# Street_Fighter_v1_1.net
KiCad netlist of a schematic drawn in EAGLE
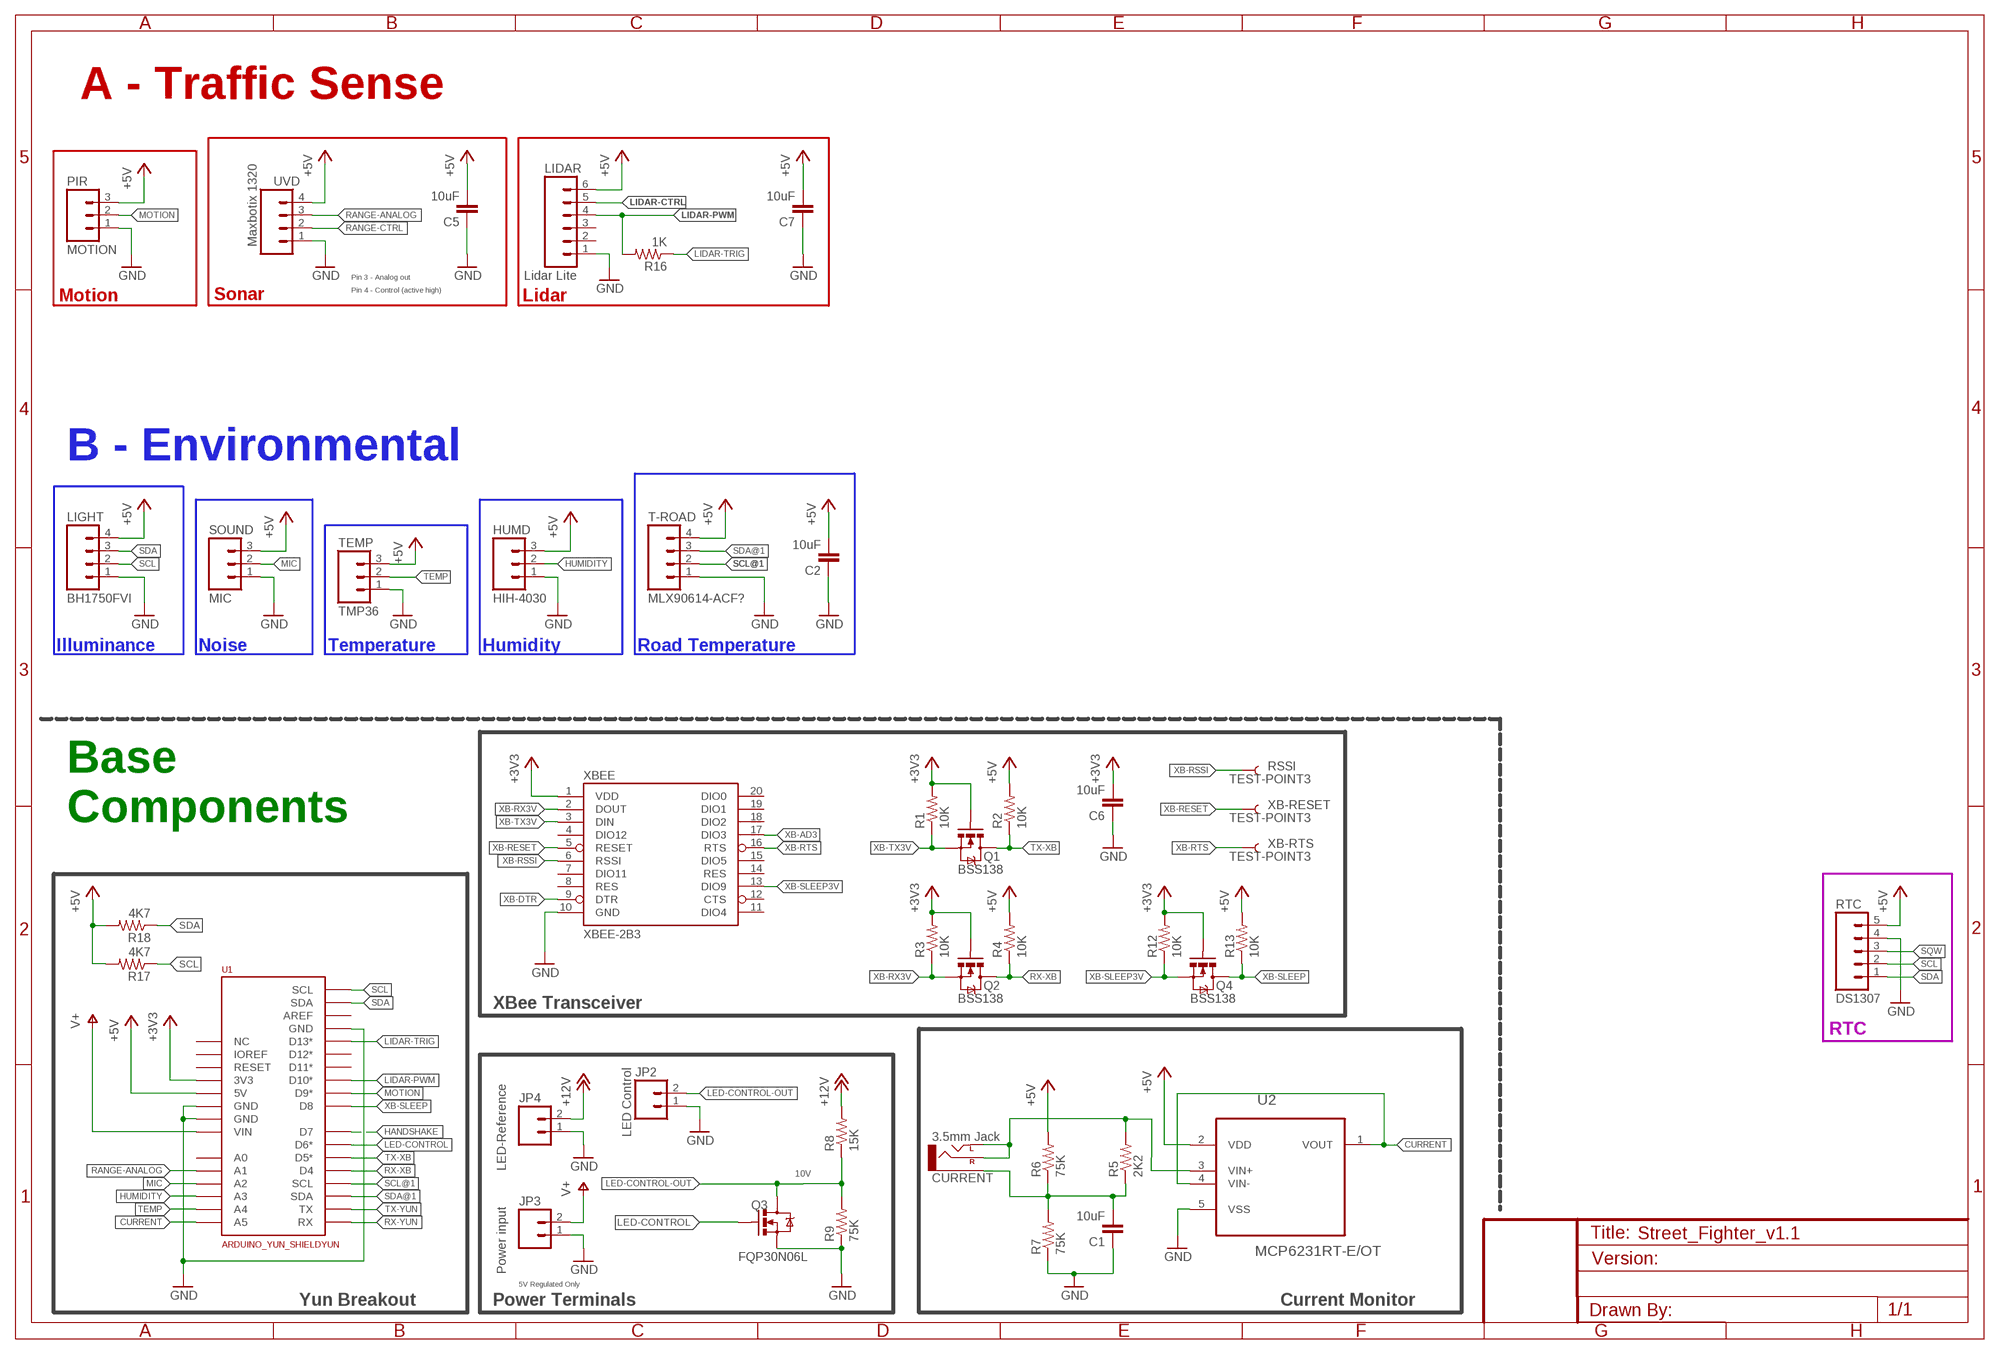
[diagram p0: schematic, sheet 1]

(export (version "E")
  (design (tool "Eeschema 10.0.6"))
  (components
    (comp (ref "C1")
      (value "10uF")
      (footprint "eagle-import:1206")
      (libsource (lib "eagle-import") (part "10UF-6.3V-20%(1206)"))
    )
    (comp (ref "C2")
      (value "10uF")
      (footprint "eagle-import:1206")
      (libsource (lib "eagle-import") (part "10UF-6.3V-20%(1206)"))
    )
    (comp (ref "C5")
      (value "10uF")
      (footprint "eagle-import:1206")
      (libsource (lib "eagle-import") (part "10UF-6.3V-20%(1206)"))
    )
    (comp (ref "C6")
      (value "10uF")
      (footprint "eagle-import:1206")
      (libsource (lib "eagle-import") (part "10UF-6.3V-20%(1206)"))
    )
    (comp (ref "C7")
      (value "10uF")
      (footprint "eagle-import:1206")
      (libsource (lib "eagle-import") (part "10UF-6.3V-20%(1206)"))
    )
    (comp (ref "CURRENT")
      (value "3.5mm Jack")
      (footprint "eagle-import:AUDIO-JACK")
      (libsource (lib "eagle-import") (part "AUDIO-JACKPTH"))
    )
    (comp (ref "HUMD")
      (value "HIH-4030")
      (footprint "eagle-import:1X03")
      (libsource (lib "eagle-import") (part "M03PTH"))
    )
    (comp (ref "JP2")
      (value "LED Control")
      (footprint "eagle-import:1X02_LONGPADS")
      (libsource (lib "eagle-import") (part "M02PTH3"))
    )
    (comp (ref "JP3")
      (value "Power input")
      (footprint "eagle-import:1X02_LONGPADS")
      (libsource (lib "eagle-import") (part "M02PTH3"))
    )
    (comp (ref "JP4")
      (value "LED-Reference")
      (footprint "eagle-import:1X02_LONGPADS")
      (libsource (lib "eagle-import") (part "M02PTH3"))
    )
    (comp (ref "LIDAR")
      (value "Lidar Lite")
      (footprint "eagle-import:1X06")
      (libsource (lib "eagle-import") (part "M06SIP"))
    )
    (comp (ref "LIGHT")
      (value "BH1750FVI")
      (footprint "eagle-import:1X04")
      (libsource (lib "eagle-import") (part "M04PTH"))
    )
    (comp (ref "PIR")
      (value "MOTION")
      (footprint "eagle-import:1X03")
      (libsource (lib "eagle-import") (part "M03PTH"))
    )
    (comp (ref "Q1")
      (value "BSS138")
      (footprint "eagle-import:SOT23")
      (libsource (lib "eagle-import") (part "MOSFET-NCHANNELBSS123LT1G"))
    )
    (comp (ref "Q2")
      (value "BSS138")
      (footprint "eagle-import:SOT23")
      (libsource (lib "eagle-import") (part "MOSFET-NCHANNELBSS123LT1G"))
    )
    (comp (ref "Q3")
      (value "FQP30N06L")
      (footprint "eagle-import:TO220V")
      (libsource (lib "eagle-import") (part "MOSFET-NCHANNELFQP30N06L"))
    )
    (comp (ref "Q4")
      (value "BSS138")
      (footprint "eagle-import:SOT23")
      (libsource (lib "eagle-import") (part "MOSFET-NCHANNELBSS123LT1G"))
    )
    (comp (ref "R1")
      (value "10K")
      (footprint "eagle-import:1206")
      (libsource (lib "eagle-import") (part "RESISTOR1206"))
    )
    (comp (ref "R2")
      (value "10K")
      (footprint "eagle-import:1206")
      (libsource (lib "eagle-import") (part "RESISTOR1206"))
    )
    (comp (ref "R3")
      (value "10K")
      (footprint "eagle-import:1206")
      (libsource (lib "eagle-import") (part "RESISTOR1206"))
    )
    (comp (ref "R4")
      (value "10K")
      (footprint "eagle-import:1206")
      (libsource (lib "eagle-import") (part "RESISTOR1206"))
    )
    (comp (ref "R5")
      (value "2K2")
      (footprint "eagle-import:1206")
      (libsource (lib "eagle-import") (part "RESISTOR1206"))
    )
    (comp (ref "R6")
      (value "75K")
      (footprint "eagle-import:1206")
      (libsource (lib "eagle-import") (part "RESISTOR1206"))
    )
    (comp (ref "R7")
      (value "75K")
      (footprint "eagle-import:1206")
      (libsource (lib "eagle-import") (part "RESISTOR1206"))
    )
    (comp (ref "R8")
      (value "15K")
      (footprint "eagle-import:1206")
      (libsource (lib "eagle-import") (part "RESISTOR1206"))
    )
    (comp (ref "R9")
      (value "75K")
      (footprint "eagle-import:1206")
      (libsource (lib "eagle-import") (part "RESISTOR1206"))
    )
    (comp (ref "R12")
      (value "10K")
      (footprint "eagle-import:1206")
      (libsource (lib "eagle-import") (part "RESISTOR1206"))
    )
    (comp (ref "R13")
      (value "10K")
      (footprint "eagle-import:1206")
      (libsource (lib "eagle-import") (part "RESISTOR1206"))
    )
    (comp (ref "R16")
      (value "1K")
      (footprint "eagle-import:1206")
      (libsource (lib "eagle-import") (part "RESISTOR1206"))
    )
    (comp (ref "R17")
      (value "4K7")
      (footprint "eagle-import:1206")
      (libsource (lib "eagle-import") (part "RESISTOR1206"))
    )
    (comp (ref "R18")
      (value "4K7")
      (footprint "eagle-import:1206")
      (libsource (lib "eagle-import") (part "RESISTOR1206"))
    )
    (comp (ref "RSSI")
      (value "TEST-POINT3")
      (footprint "eagle-import:PAD.03X.03")
      (libsource (lib "eagle-import") (part "TEST-POINT3"))
    )
    (comp (ref "RTC")
      (value "DS1307")
      (footprint "eagle-import:1X05")
      (libsource (lib "eagle-import") (part "M05PTH"))
    )
    (comp (ref "SOUND")
      (value "MIC")
      (footprint "eagle-import:1X03")
      (libsource (lib "eagle-import") (part "M03PTH"))
    )
    (comp (ref "T-ROAD")
      (value "MLX90614-ACF?")
      (footprint "eagle-import:1X04")
      (libsource (lib "eagle-import") (part "M04PTH"))
    )
    (comp (ref "TEMP")
      (value "TMP36")
      (footprint "eagle-import:1X03")
      (libsource (lib "eagle-import") (part "M03PTH"))
    )
    (comp (ref "U1")
      (value "ARDUINO_YUN_SHIELDYUN")
      (footprint "eagle-import:DUEMILANOVE_VIAS")
      (libsource (lib "eagle-import") (part "ARDUINO_YUN_SHIELDYUN"))
    )
    (comp (ref "U2")
      (value "MCP6231RT-E/OT")
      (footprint "eagle-import:SOT95P270X145-5N")
      (libsource (lib "eagle-import") (part "MCP6231RT-E/OT"))
    )
    (comp (ref "UVD")
      (value "Maxbotix 1320")
      (footprint "eagle-import:1X04")
      (libsource (lib "eagle-import") (part "M04PTH"))
    )
    (comp (ref "XB-RESET")
      (value "TEST-POINT3")
      (footprint "eagle-import:PAD.03X.03")
      (libsource (lib "eagle-import") (part "TEST-POINT3"))
    )
    (comp (ref "XB-RTS")
      (value "TEST-POINT3")
      (footprint "eagle-import:PAD.03X.03")
      (libsource (lib "eagle-import") (part "TEST-POINT3"))
    )
    (comp (ref "XBEE")
      (value "XBEE-2B3")
      (footprint "eagle-import:XBEE-SMD")
      (libsource (lib "eagle-import") (part "XBEE-2B3"))
    )
  )
  (nets
    (net (code "1") (name "+3V3") (class "Default")
      (node (ref "C6") (pin "2") (pinfunction "2_2") (pintype "passive"))
      (node (ref "Q1") (pin "1") (pinfunction "G_1") (pintype "passive"))
      (node (ref "Q2") (pin "1") (pinfunction "G_1") (pintype "passive"))
      (node (ref "Q4") (pin "1") (pinfunction "G_1") (pintype "passive"))
      (node (ref "R1") (pin "2") (pinfunction "2_2") (pintype "passive"))
      (node (ref "R12") (pin "2") (pinfunction "2_2") (pintype "passive"))
      (node (ref "R3") (pin "2") (pinfunction "2_2") (pintype "passive"))
      (node (ref "U1") (pin "3V3") (pinfunction "3V3_3V3") (pintype "power_in"))
      (node (ref "XBEE") (pin "1") (pinfunction "VDD_1") (pintype "power_in"))
    )
    (net (code "2") (name "+5V") (class "Default")
      (node (ref "C2") (pin "2") (pinfunction "2_2") (pintype "passive"))
      (node (ref "C5") (pin "2") (pinfunction "2_2") (pintype "passive"))
      (node (ref "C7") (pin "2") (pinfunction "2_2") (pintype "passive"))
      (node (ref "HUMD") (pin "3") (pinfunction "3_3") (pintype "passive"))
      (node (ref "LIDAR") (pin "6") (pinfunction "6_6") (pintype "passive"))
      (node (ref "LIGHT") (pin "4") (pinfunction "4_4") (pintype "passive"))
      (node (ref "PIR") (pin "3") (pinfunction "3_3") (pintype "passive"))
      (node (ref "R13") (pin "2") (pinfunction "2_2") (pintype "passive"))
      (node (ref "R17") (pin "2") (pinfunction "2_2") (pintype "passive"))
      (node (ref "R18") (pin "2") (pinfunction "2_2") (pintype "passive"))
      (node (ref "R2") (pin "2") (pinfunction "2_2") (pintype "passive"))
      (node (ref "R4") (pin "2") (pinfunction "2_2") (pintype "passive"))
      (node (ref "R6") (pin "2") (pinfunction "2_2") (pintype "passive"))
      (node (ref "RTC") (pin "5") (pinfunction "5_5") (pintype "passive"))
      (node (ref "SOUND") (pin "3") (pinfunction "3_3") (pintype "passive"))
      (node (ref "T-ROAD") (pin "4") (pinfunction "4_4") (pintype "passive"))
      (node (ref "TEMP") (pin "3") (pinfunction "3_3") (pintype "passive"))
      (node (ref "U1") (pin "5V") (pinfunction "5V_5V") (pintype "power_in"))
      (node (ref "U2") (pin "2") (pinfunction "VDD_2") (pintype "power_in"))
      (node (ref "UVD") (pin "4") (pinfunction "4_4") (pintype "passive"))
    )
    (net (code "3") (name "+12V") (class "Default")
      (node (ref "JP4") (pin "2") (pinfunction "2_2") (pintype "passive"))
      (node (ref "R8") (pin "2") (pinfunction "2_2") (pintype "passive"))
    )
    (net (code "4") (name "CURRENT") (class "Default")
      (node (ref "U1") (pin "A5") (pinfunction "A5_A5") (pintype "bidirectional"))
      (node (ref "U2") (pin "1") (pinfunction "VOUT_1") (pintype "output"))
      (node (ref "U2") (pin "4") (pinfunction "VIN-_4") (pintype "input"))
    )
    (net (code "5") (name "GND") (class "Default")
      (node (ref "C1") (pin "1") (pinfunction "1_1") (pintype "passive"))
      (node (ref "C2") (pin "1") (pinfunction "1_1") (pintype "passive"))
      (node (ref "C5") (pin "1") (pinfunction "1_1") (pintype "passive"))
      (node (ref "C6") (pin "1") (pinfunction "1_1") (pintype "passive"))
      (node (ref "C7") (pin "1") (pinfunction "1_1") (pintype "passive"))
      (node (ref "HUMD") (pin "1") (pinfunction "1_1") (pintype "passive"))
      (node (ref "JP2") (pin "1") (pinfunction "1_1") (pintype "passive"))
      (node (ref "JP3") (pin "1") (pinfunction "1_1") (pintype "passive"))
      (node (ref "JP4") (pin "1") (pinfunction "1_1") (pintype "passive"))
      (node (ref "LIDAR") (pin "1") (pinfunction "1_1") (pintype "passive"))
      (node (ref "LIGHT") (pin "1") (pinfunction "1_1") (pintype "passive"))
      (node (ref "PIR") (pin "1") (pinfunction "1_1") (pintype "passive"))
      (node (ref "Q3") (pin "3") (pinfunction "S_3") (pintype "passive"))
      (node (ref "R7") (pin "1") (pinfunction "1_1") (pintype "passive"))
      (node (ref "R9") (pin "1") (pinfunction "1_1") (pintype "passive"))
      (node (ref "RTC") (pin "4") (pinfunction "4_4") (pintype "passive"))
      (node (ref "SOUND") (pin "1") (pinfunction "1_1") (pintype "passive"))
      (node (ref "T-ROAD") (pin "1") (pinfunction "1_1") (pintype "passive"))
      (node (ref "TEMP") (pin "1") (pinfunction "1_1") (pintype "passive"))
      (node (ref "U1") (pin "GND") (pinfunction "GND_GND") (pintype "power_in"))
      (node (ref "U1") (pin "GND@0") (pinfunction "GND_GND@0") (pintype "power_in"))
      (node (ref "U1") (pin "GND@1") (pinfunction "GND_GND@1") (pintype "power_in"))
      (node (ref "U2") (pin "5") (pinfunction "VSS_5") (pintype "passive"))
      (node (ref "UVD") (pin "1") (pinfunction "1_1") (pintype "passive"))
      (node (ref "XBEE") (pin "10") (pinfunction "GND_10") (pintype "power_in"))
    )
    (net (code "6") (name "HANDSHAKE") (class "Default")
      (node (ref "U1") (pin "7") (pinfunction "D7_7") (pintype "bidirectional"))
    )
    (net (code "7") (name "HUMIDITY") (class "Default")
      (node (ref "HUMD") (pin "2") (pinfunction "2_2") (pintype "passive"))
      (node (ref "U1") (pin "A3") (pinfunction "A3_A3") (pintype "bidirectional"))
    )
    (net (code "8") (name "LED-CONTROL") (class "Default")
      (node (ref "Q3") (pin "1") (pinfunction "G_1") (pintype "passive"))
      (node (ref "U1") (pin "6") (pinfunction "D6*_6") (pintype "bidirectional"))
    )
    (net (code "9") (name "LED-CONTROL-OUT") (class "Default")
      (node (ref "JP2") (pin "2") (pinfunction "2_2") (pintype "passive"))
      (node (ref "Q3") (pin "2") (pinfunction "D_2") (pintype "passive"))
      (node (ref "R8") (pin "1") (pinfunction "1_1") (pintype "passive"))
      (node (ref "R9") (pin "2") (pinfunction "2_2") (pintype "passive"))
    )
    (net (code "10") (name "LIDAR-CTRL") (class "Default")
      (node (ref "LIDAR") (pin "5") (pinfunction "5_5") (pintype "passive"))
    )
    (net (code "11") (name "LIDAR-PWM") (class "Default")
      (node (ref "LIDAR") (pin "4") (pinfunction "4_4") (pintype "passive"))
      (node (ref "R16") (pin "2") (pinfunction "2_2") (pintype "passive"))
      (node (ref "U1") (pin "10") (pinfunction "D10*_10") (pintype "bidirectional"))
    )
    (net (code "12") (name "LIDAR-TRIG") (class "Default")
      (node (ref "R16") (pin "1") (pinfunction "1_1") (pintype "passive"))
      (node (ref "U1") (pin "13") (pinfunction "D13*_13") (pintype "bidirectional"))
    )
    (net (code "13") (name "MIC") (class "Default")
      (node (ref "SOUND") (pin "2") (pinfunction "2_2") (pintype "passive"))
      (node (ref "U1") (pin "A2") (pinfunction "A2_A2") (pintype "bidirectional"))
    )
    (net (code "14") (name "MOTION") (class "Default")
      (node (ref "PIR") (pin "2") (pinfunction "2_2") (pintype "passive"))
      (node (ref "U1") (pin "9") (pinfunction "D9*_9") (pintype "bidirectional"))
    )
    (net (code "15") (name "Net-(C1-Pad2)") (class "Default")
      (node (ref "C1") (pin "2") (pinfunction "2_2") (pintype "passive"))
      (node (ref "CURRENT") (pin "SLEEVE") (pinfunction "SLEEVE_SLEEVE") (pintype "bidirectional"))
      (node (ref "R5") (pin "1") (pinfunction "1_1") (pintype "passive"))
      (node (ref "R6") (pin "1") (pinfunction "1_1") (pintype "passive"))
      (node (ref "R7") (pin "2") (pinfunction "2_2") (pintype "passive"))
    )
    (net (code "16") (name "Net-(CURRENT-LEFT)") (class "Default")
      (node (ref "CURRENT") (pin "RING") (pinfunction "RIGHT_RING") (pintype "bidirectional"))
      (node (ref "CURRENT") (pin "TIP") (pinfunction "LEFT_TIP") (pintype "bidirectional"))
      (node (ref "R5") (pin "2") (pinfunction "2_2") (pintype "passive"))
      (node (ref "U2") (pin "3") (pinfunction "VIN+_3") (pintype "input"))
    )
    (net (code "17") (name "RANGE-ANALOG") (class "Default")
      (node (ref "U1") (pin "A1") (pinfunction "A1_A1") (pintype "bidirectional"))
      (node (ref "UVD") (pin "3") (pinfunction "3_3") (pintype "passive"))
    )
    (net (code "18") (name "RANGE-CTRL") (class "Default")
      (node (ref "UVD") (pin "2") (pinfunction "2_2") (pintype "passive"))
    )
    (net (code "19") (name "RX-XB") (class "Default")
      (node (ref "Q2") (pin "3") (pinfunction "D_3") (pintype "passive"))
      (node (ref "R4") (pin "1") (pinfunction "1_1") (pintype "passive"))
      (node (ref "U1") (pin "D4") (pinfunction "D4_D4") (pintype "bidirectional"))
    )
    (net (code "20") (name "RX-YUN") (class "Default")
      (node (ref "U1") (pin "0") (pinfunction "RX_0") (pintype "bidirectional"))
    )
    (net (code "21") (name "SCL") (class "Default")
      (node (ref "LIGHT") (pin "2") (pinfunction "2_2") (pintype "passive"))
      (node (ref "R17") (pin "1") (pinfunction "1_1") (pintype "passive"))
      (node (ref "RTC") (pin "2") (pinfunction "2_2") (pintype "passive"))
      (node (ref "U1") (pin "3@1") (pinfunction "SCL_3@1") (pintype "bidirectional"))
    )
    (net (code "22") (name "SCL@1") (class "Default")
      (node (ref "T-ROAD") (pin "2") (pinfunction "2_2") (pintype "passive"))
      (node (ref "U1") (pin "3") (pinfunction "SCL_3") (pintype "bidirectional"))
    )
    (net (code "23") (name "SDA") (class "Default")
      (node (ref "LIGHT") (pin "3") (pinfunction "3_3") (pintype "passive"))
      (node (ref "R18") (pin "1") (pinfunction "1_1") (pintype "passive"))
      (node (ref "RTC") (pin "1") (pinfunction "1_1") (pintype "passive"))
      (node (ref "U1") (pin "2@1") (pinfunction "SDA_2@1") (pintype "bidirectional"))
    )
    (net (code "24") (name "SDA@1") (class "Default")
      (node (ref "T-ROAD") (pin "3") (pinfunction "3_3") (pintype "passive"))
      (node (ref "U1") (pin "2") (pinfunction "SDA_2") (pintype "bidirectional"))
    )
    (net (code "25") (name "SQW") (class "Default")
      (node (ref "RTC") (pin "3") (pinfunction "3_3") (pintype "passive"))
    )
    (net (code "26") (name "TEMP") (class "Default")
      (node (ref "TEMP") (pin "2") (pinfunction "2_2") (pintype "passive"))
      (node (ref "U1") (pin "A4") (pinfunction "A4_A4") (pintype "bidirectional"))
    )
    (net (code "27") (name "TX-XB") (class "Default")
      (node (ref "Q1") (pin "3") (pinfunction "D_3") (pintype "passive"))
      (node (ref "R2") (pin "1") (pinfunction "1_1") (pintype "passive"))
      (node (ref "U1") (pin "5") (pinfunction "D5*_5") (pintype "bidirectional"))
    )
    (net (code "28") (name "TX-YUN") (class "Default")
      (node (ref "U1") (pin "1") (pinfunction "TX_1") (pintype "bidirectional"))
    )
    (net (code "29") (name "V+") (class "Default")
      (node (ref "JP3") (pin "2") (pinfunction "2_2") (pintype "passive"))
      (node (ref "U1") (pin "VIN") (pinfunction "VIN_VIN") (pintype "power_in"))
    )
    (net (code "30") (name "XB-AD3") (class "Default")
      (node (ref "XBEE") (pin "17") (pinfunction "DIO3_17") (pintype "bidirectional"))
    )
    (net (code "31") (name "XB-DTR") (class "Default")
      (node (ref "XBEE") (pin "9") (pinfunction "DTR_9") (pintype "bidirectional"))
    )
    (net (code "32") (name "XB-RESET") (class "Default")
      (node (ref "XB-RESET") (pin "P$1") (pinfunction "1_P$1") (pintype "bidirectional"))
      (node (ref "XBEE") (pin "5") (pinfunction "RESET_5") (pintype "input"))
    )
    (net (code "33") (name "XB-RSSI") (class "Default")
      (node (ref "RSSI") (pin "P$1") (pinfunction "1_P$1") (pintype "bidirectional"))
      (node (ref "XBEE") (pin "6") (pinfunction "RSSI_6") (pintype "bidirectional"))
    )
    (net (code "34") (name "XB-RTS") (class "Default")
      (node (ref "XB-RTS") (pin "P$1") (pinfunction "1_P$1") (pintype "bidirectional"))
      (node (ref "XBEE") (pin "16") (pinfunction "RTS_16") (pintype "input"))
    )
    (net (code "35") (name "XB-RX3V") (class "Default")
      (node (ref "Q2") (pin "2") (pinfunction "S_2") (pintype "passive"))
      (node (ref "R3") (pin "1") (pinfunction "1_1") (pintype "passive"))
      (node (ref "XBEE") (pin "2") (pinfunction "DOUT_2") (pintype "output"))
    )
    (net (code "36") (name "XB-SLEEP") (class "Default")
      (node (ref "Q4") (pin "3") (pinfunction "D_3") (pintype "passive"))
      (node (ref "R13") (pin "1") (pinfunction "1_1") (pintype "passive"))
      (node (ref "U1") (pin "8") (pinfunction "D8_8") (pintype "bidirectional"))
    )
    (net (code "37") (name "XB-SLEEP3V") (class "Default")
      (node (ref "Q4") (pin "2") (pinfunction "S_2") (pintype "passive"))
      (node (ref "R12") (pin "1") (pinfunction "1_1") (pintype "passive"))
      (node (ref "XBEE") (pin "13") (pinfunction "DIO9_13") (pintype "bidirectional"))
    )
    (net (code "38") (name "XB-TX3V") (class "Default")
      (node (ref "Q1") (pin "2") (pinfunction "S_2") (pintype "passive"))
      (node (ref "R1") (pin "1") (pinfunction "1_1") (pintype "passive"))
      (node (ref "XBEE") (pin "3") (pinfunction "DIN_3") (pintype "input"))
    )
    (net (code "39") (name "unconnected-(LIDAR-Pad2)") (class "Default")
      (node (ref "LIDAR") (pin "2") (pinfunction "2_2") (pintype "passive"))
    )
    (net (code "40") (name "unconnected-(LIDAR-Pad3)") (class "Default")
      (node (ref "LIDAR") (pin "3") (pinfunction "3_3") (pintype "passive"))
    )
    (net (code "41") (name "unconnected-(U1-D11*-Pad11)") (class "Default")
      (node (ref "U1") (pin "11") (pinfunction "D11*_11") (pintype "bidirectional"))
    )
    (net (code "42") (name "unconnected-(U1-D12*-Pad12)") (class "Default")
      (node (ref "U1") (pin "12") (pinfunction "D12*_12") (pintype "bidirectional"))
    )
    (net (code "43") (name "unconnected-(U1-PadA0)") (class "Default")
      (node (ref "U1") (pin "A0") (pinfunction "A0_A0") (pintype "bidirectional"))
    )
    (net (code "44") (name "unconnected-(U1-PadAREF)") (class "Default")
      (node (ref "U1") (pin "AREF") (pinfunction "AREF_AREF") (pintype "bidirectional"))
    )
    (net (code "45") (name "unconnected-(U1-PadIOREF)") (class "Default")
      (node (ref "U1") (pin "IOREF") (pinfunction "IOREF_IOREF") (pintype "bidirectional"))
    )
    (net (code "46") (name "unconnected-(U1-PadNC)") (class "Default")
      (node (ref "U1") (pin "NC") (pinfunction "NC_NC") (pintype "no_connect"))
    )
    (net (code "47") (name "unconnected-(U1-PadRESET)") (class "Default")
      (node (ref "U1") (pin "RESET") (pinfunction "RESET_RESET") (pintype "bidirectional"))
    )
    (net (code "48") (name "unconnected-(XBEE-CTS-Pad12)") (class "Default")
      (node (ref "XBEE") (pin "12") (pinfunction "CTS_12") (pintype "output"))
    )
    (net (code "49") (name "unconnected-(XBEE-DIO0-Pad20)") (class "Default")
      (node (ref "XBEE") (pin "20") (pinfunction "DIO0_20") (pintype "bidirectional"))
    )
    (net (code "50") (name "unconnected-(XBEE-DIO1-Pad19)") (class "Default")
      (node (ref "XBEE") (pin "19") (pinfunction "DIO1_19") (pintype "bidirectional"))
    )
    (net (code "51") (name "unconnected-(XBEE-DIO2-Pad18)") (class "Default")
      (node (ref "XBEE") (pin "18") (pinfunction "DIO2_18") (pintype "bidirectional"))
    )
    (net (code "52") (name "unconnected-(XBEE-DIO4-Pad11)") (class "Default")
      (node (ref "XBEE") (pin "11") (pinfunction "DIO4_11") (pintype "bidirectional"))
    )
    (net (code "53") (name "unconnected-(XBEE-DIO5-Pad15)") (class "Default")
      (node (ref "XBEE") (pin "15") (pinfunction "DIO5_15") (pintype "bidirectional"))
    )
    (net (code "54") (name "unconnected-(XBEE-DIO11-Pad7)") (class "Default")
      (node (ref "XBEE") (pin "7") (pinfunction "DIO11_7") (pintype "bidirectional"))
    )
    (net (code "55") (name "unconnected-(XBEE-DIO12-Pad4)") (class "Default")
      (node (ref "XBEE") (pin "4") (pinfunction "DIO12_4") (pintype "bidirectional"))
    )
    (net (code "56") (name "unconnected-(XBEE-RES-Pad8)") (class "Default")
      (node (ref "XBEE") (pin "8") (pinfunction "RES_8") (pintype "bidirectional"))
    )
    (net (code "57") (name "unconnected-(XBEE-RES-Pad14)") (class "Default")
      (node (ref "XBEE") (pin "14") (pinfunction "RES_14") (pintype "bidirectional"))
    )
  )
)
